# ADC_1_0.net
KiCad netlist of a schematic drawn in EAGLE
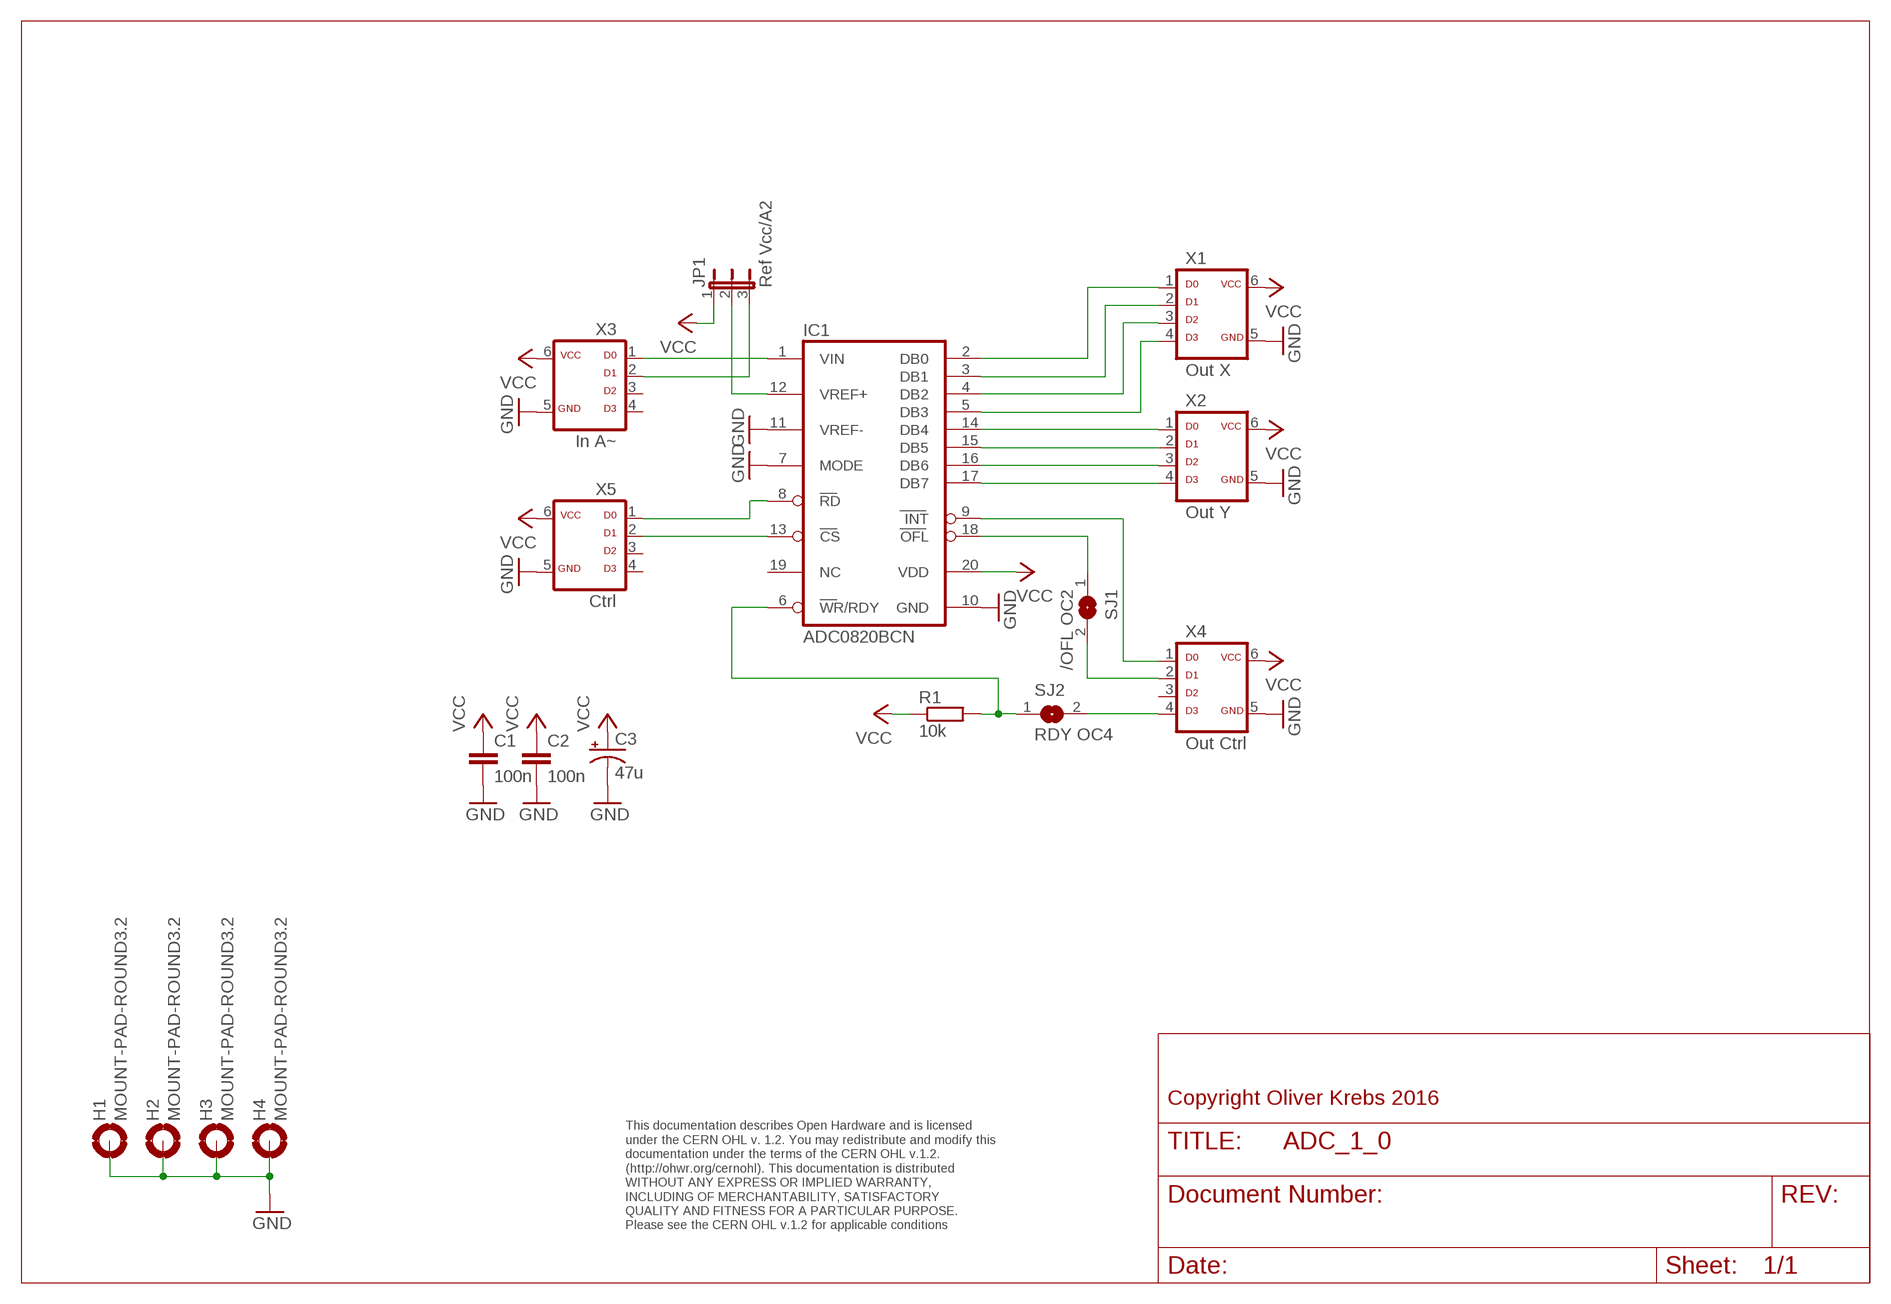
[diagram p0: schematic, sheet 1]

(export (version "E")
  (design (tool "Eeschema 10.0.6"))
  (components
    (comp (ref "C1")
      (value "100n")
      (footprint "eagle-import:CAP-PTH-5MM")
      (libsource (lib "eagle-import") (part "CAPPTH1"))
    )
    (comp (ref "C2")
      (value "100n")
      (footprint "eagle-import:CAP-PTH-5MM")
      (libsource (lib "eagle-import") (part "CAPPTH1"))
    )
    (comp (ref "C3")
      (value "47u")
      (footprint "eagle-import:CPOL-RADIAL-100UF-25V")
      (libsource (lib "eagle-import") (part "CAP_POLPTH1"))
    )
    (comp (ref "H1")
      (value "MOUNT-PAD-ROUND3.2")
      (footprint "eagle-import:3,2-PAD")
      (libsource (lib "eagle-import") (part "MOUNT-PAD-ROUND3.2"))
    )
    (comp (ref "H2")
      (value "MOUNT-PAD-ROUND3.2")
      (footprint "eagle-import:3,2-PAD")
      (libsource (lib "eagle-import") (part "MOUNT-PAD-ROUND3.2"))
    )
    (comp (ref "H3")
      (value "MOUNT-PAD-ROUND3.2")
      (footprint "eagle-import:3,2-PAD")
      (libsource (lib "eagle-import") (part "MOUNT-PAD-ROUND3.2"))
    )
    (comp (ref "H4")
      (value "MOUNT-PAD-ROUND3.2")
      (footprint "eagle-import:3,2-PAD")
      (libsource (lib "eagle-import") (part "MOUNT-PAD-ROUND3.2"))
    )
    (comp (ref "IC1")
      (value "ADC0820BCN")
      (footprint "eagle-import:DIL20")
      (fields (field (name "MF") "NATIONAL SEMICONDUCTOR") (field (name "MPN") "ADC0820CCN/NOPB."))
      (libsource (lib "eagle-import") (part "ADC0820BCN"))
    )
    (comp (ref "JP1")
      (value "Ref Vcc/A2")
      (footprint "eagle-import:JP2-U")
      (libsource (lib "eagle-import") (part "JP2EJP2-U"))
    )
    (comp (ref "R1")
      (value "10k")
      (footprint "eagle-import:0207_10")
      (libsource (lib "eagle-import") (part "R-EU_0207/10"))
    )
    (comp (ref "SJ1")
      (value "/OFL OC2")
      (footprint "eagle-import:SJ")
      (libsource (lib "eagle-import") (part "SJ"))
    )
    (comp (ref "SJ2")
      (value "RDY OC4")
      (footprint "eagle-import:SJ")
      (libsource (lib "eagle-import") (part "SJ"))
    )
    (comp (ref "X1")
      (value "Out X")
      (footprint "eagle-import:ML-6")
      (libsource (lib "eagle-import") (part "ML6D"))
    )
    (comp (ref "X2")
      (value "Out Y")
      (footprint "eagle-import:ML-6")
      (libsource (lib "eagle-import") (part "ML6D"))
    )
    (comp (ref "X3")
      (value "In A~")
      (footprint "eagle-import:ML-6")
      (libsource (lib "eagle-import") (part "ML6D"))
    )
    (comp (ref "X4")
      (value "Out Ctrl")
      (footprint "eagle-import:ML-6")
      (libsource (lib "eagle-import") (part "ML6D"))
    )
    (comp (ref "X5")
      (value "Ctrl")
      (footprint "eagle-import:ML-6")
      (libsource (lib "eagle-import") (part "ML6D"))
    )
  )
  (nets
    (net (code "1") (name "GND") (class "Default")
      (node (ref "C1") (pin "2") (pinfunction "2_2") (pintype "passive"))
      (node (ref "C2") (pin "2") (pinfunction "2_2") (pintype "passive"))
      (node (ref "C3") (pin "2") (pinfunction "-_2") (pintype "passive"))
      (node (ref "H1") (pin "B3,2") (pinfunction "MOUNT_B3,2") (pintype "passive"))
      (node (ref "H2") (pin "B3,2") (pinfunction "MOUNT_B3,2") (pintype "passive"))
      (node (ref "H3") (pin "B3,2") (pinfunction "MOUNT_B3,2") (pintype "passive"))
      (node (ref "H4") (pin "B3,2") (pinfunction "MOUNT_B3,2") (pintype "passive"))
      (node (ref "IC1") (pin "10") (pinfunction "GND_10") (pintype "power_in"))
      (node (ref "IC1") (pin "11") (pinfunction "VREF-_11") (pintype "passive"))
      (node (ref "IC1") (pin "7") (pinfunction "MODE_7") (pintype "input"))
      (node (ref "X1") (pin "5") (pinfunction "5_5") (pintype "passive"))
      (node (ref "X2") (pin "5") (pinfunction "5_5") (pintype "passive"))
      (node (ref "X3") (pin "5") (pinfunction "5_5") (pintype "passive"))
      (node (ref "X4") (pin "5") (pinfunction "5_5") (pintype "passive"))
      (node (ref "X5") (pin "5") (pinfunction "5_5") (pintype "passive"))
    )
    (net (code "2") (name "Net-(IC1-CS)") (class "Default")
      (node (ref "IC1") (pin "13") (pinfunction "CS_13") (pintype "input"))
      (node (ref "X5") (pin "2") (pinfunction "2_2") (pintype "passive"))
    )
    (net (code "3") (name "Net-(IC1-DB0)") (class "Default")
      (node (ref "IC1") (pin "2") (pinfunction "DB0_2") (pintype "tri_state"))
      (node (ref "X1") (pin "1") (pinfunction "1_1") (pintype "passive"))
    )
    (net (code "4") (name "Net-(IC1-DB1)") (class "Default")
      (node (ref "IC1") (pin "3") (pinfunction "DB1_3") (pintype "tri_state"))
      (node (ref "X1") (pin "2") (pinfunction "2_2") (pintype "passive"))
    )
    (net (code "5") (name "Net-(IC1-DB2)") (class "Default")
      (node (ref "IC1") (pin "4") (pinfunction "DB2_4") (pintype "tri_state"))
      (node (ref "X1") (pin "3") (pinfunction "3_3") (pintype "passive"))
    )
    (net (code "6") (name "Net-(IC1-DB3)") (class "Default")
      (node (ref "IC1") (pin "5") (pinfunction "DB3_5") (pintype "tri_state"))
      (node (ref "X1") (pin "4") (pinfunction "4_4") (pintype "passive"))
    )
    (net (code "7") (name "Net-(IC1-DB4)") (class "Default")
      (node (ref "IC1") (pin "14") (pinfunction "DB4_14") (pintype "tri_state"))
      (node (ref "X2") (pin "1") (pinfunction "1_1") (pintype "passive"))
    )
    (net (code "8") (name "Net-(IC1-DB5)") (class "Default")
      (node (ref "IC1") (pin "15") (pinfunction "DB5_15") (pintype "tri_state"))
      (node (ref "X2") (pin "2") (pinfunction "2_2") (pintype "passive"))
    )
    (net (code "9") (name "Net-(IC1-DB6)") (class "Default")
      (node (ref "IC1") (pin "16") (pinfunction "DB6_16") (pintype "tri_state"))
      (node (ref "X2") (pin "3") (pinfunction "3_3") (pintype "passive"))
    )
    (net (code "10") (name "Net-(IC1-DB7)") (class "Default")
      (node (ref "IC1") (pin "17") (pinfunction "DB7_17") (pintype "tri_state"))
      (node (ref "X2") (pin "4") (pinfunction "4_4") (pintype "passive"))
    )
    (net (code "11") (name "Net-(IC1-INT)") (class "Default")
      (node (ref "IC1") (pin "9") (pinfunction "INT_9") (pintype "output"))
      (node (ref "X4") (pin "1") (pinfunction "1_1") (pintype "passive"))
    )
    (net (code "12") (name "Net-(IC1-OFL)") (class "Default")
      (node (ref "IC1") (pin "18") (pinfunction "OFL_18") (pintype "output"))
      (node (ref "SJ1") (pin "1") (pinfunction "1_1") (pintype "passive"))
    )
    (net (code "13") (name "Net-(IC1-RD)") (class "Default")
      (node (ref "IC1") (pin "8") (pinfunction "RD_8") (pintype "input"))
      (node (ref "X5") (pin "1") (pinfunction "1_1") (pintype "passive"))
    )
    (net (code "14") (name "Net-(IC1-VIN)") (class "Default")
      (node (ref "IC1") (pin "1") (pinfunction "VIN_1") (pintype "input"))
      (node (ref "X3") (pin "1") (pinfunction "1_1") (pintype "passive"))
    )
    (net (code "15") (name "Net-(IC1-VREF+)") (class "Default")
      (node (ref "IC1") (pin "12") (pinfunction "VREF+_12") (pintype "passive"))
      (node (ref "JP1") (pin "2") (pinfunction "2_2") (pintype "passive"))
    )
    (net (code "16") (name "Net-(IC1-WR{slash}RDY)") (class "Default")
      (node (ref "IC1") (pin "6") (pinfunction "WR/RDY_6") (pintype "bidirectional"))
      (node (ref "R1") (pin "2") (pinfunction "2_2") (pintype "passive"))
      (node (ref "SJ2") (pin "1") (pinfunction "1_1") (pintype "passive"))
    )
    (net (code "17") (name "Net-(JP1-Pad3)") (class "Default")
      (node (ref "JP1") (pin "3") (pinfunction "3_3") (pintype "passive"))
      (node (ref "X3") (pin "2") (pinfunction "2_2") (pintype "passive"))
    )
    (net (code "18") (name "Net-(SJ1-Pad2)") (class "Default")
      (node (ref "SJ1") (pin "2") (pinfunction "2_2") (pintype "passive"))
      (node (ref "X4") (pin "2") (pinfunction "2_2") (pintype "passive"))
    )
    (net (code "19") (name "Net-(SJ2-Pad2)") (class "Default")
      (node (ref "SJ2") (pin "2") (pinfunction "2_2") (pintype "passive"))
      (node (ref "X4") (pin "4") (pinfunction "4_4") (pintype "passive"))
    )
    (net (code "20") (name "VCC") (class "Default")
      (node (ref "C1") (pin "1") (pinfunction "1_1") (pintype "passive"))
      (node (ref "C2") (pin "1") (pinfunction "1_1") (pintype "passive"))
      (node (ref "C3") (pin "1") (pinfunction "+_1") (pintype "passive"))
      (node (ref "IC1") (pin "20") (pinfunction "VDD_20") (pintype "power_in"))
      (node (ref "JP1") (pin "1") (pinfunction "1_1") (pintype "passive"))
      (node (ref "R1") (pin "1") (pinfunction "1_1") (pintype "passive"))
      (node (ref "X1") (pin "6") (pinfunction "6_6") (pintype "passive"))
      (node (ref "X2") (pin "6") (pinfunction "6_6") (pintype "passive"))
      (node (ref "X3") (pin "6") (pinfunction "6_6") (pintype "passive"))
      (node (ref "X4") (pin "6") (pinfunction "6_6") (pintype "passive"))
      (node (ref "X5") (pin "6") (pinfunction "6_6") (pintype "passive"))
    )
    (net (code "21") (name "unconnected-(IC1-NC-Pad19)") (class "Default")
      (node (ref "IC1") (pin "19") (pinfunction "NC_19") (pintype "no_connect"))
    )
    (net (code "22") (name "unconnected-(X3-Pad3)") (class "Default")
      (node (ref "X3") (pin "3") (pinfunction "3_3") (pintype "passive"))
    )
    (net (code "23") (name "unconnected-(X3-Pad4)") (class "Default")
      (node (ref "X3") (pin "4") (pinfunction "4_4") (pintype "passive"))
    )
    (net (code "24") (name "unconnected-(X4-Pad3)") (class "Default")
      (node (ref "X4") (pin "3") (pinfunction "3_3") (pintype "passive"))
    )
    (net (code "25") (name "unconnected-(X5-Pad3)") (class "Default")
      (node (ref "X5") (pin "3") (pinfunction "3_3") (pintype "passive"))
    )
    (net (code "26") (name "unconnected-(X5-Pad4)") (class "Default")
      (node (ref "X5") (pin "4") (pinfunction "4_4") (pintype "passive"))
    )
  )
)
